# uBlox_camM8_breakout.net
KiCad netlist of a schematic drawn in EAGLE
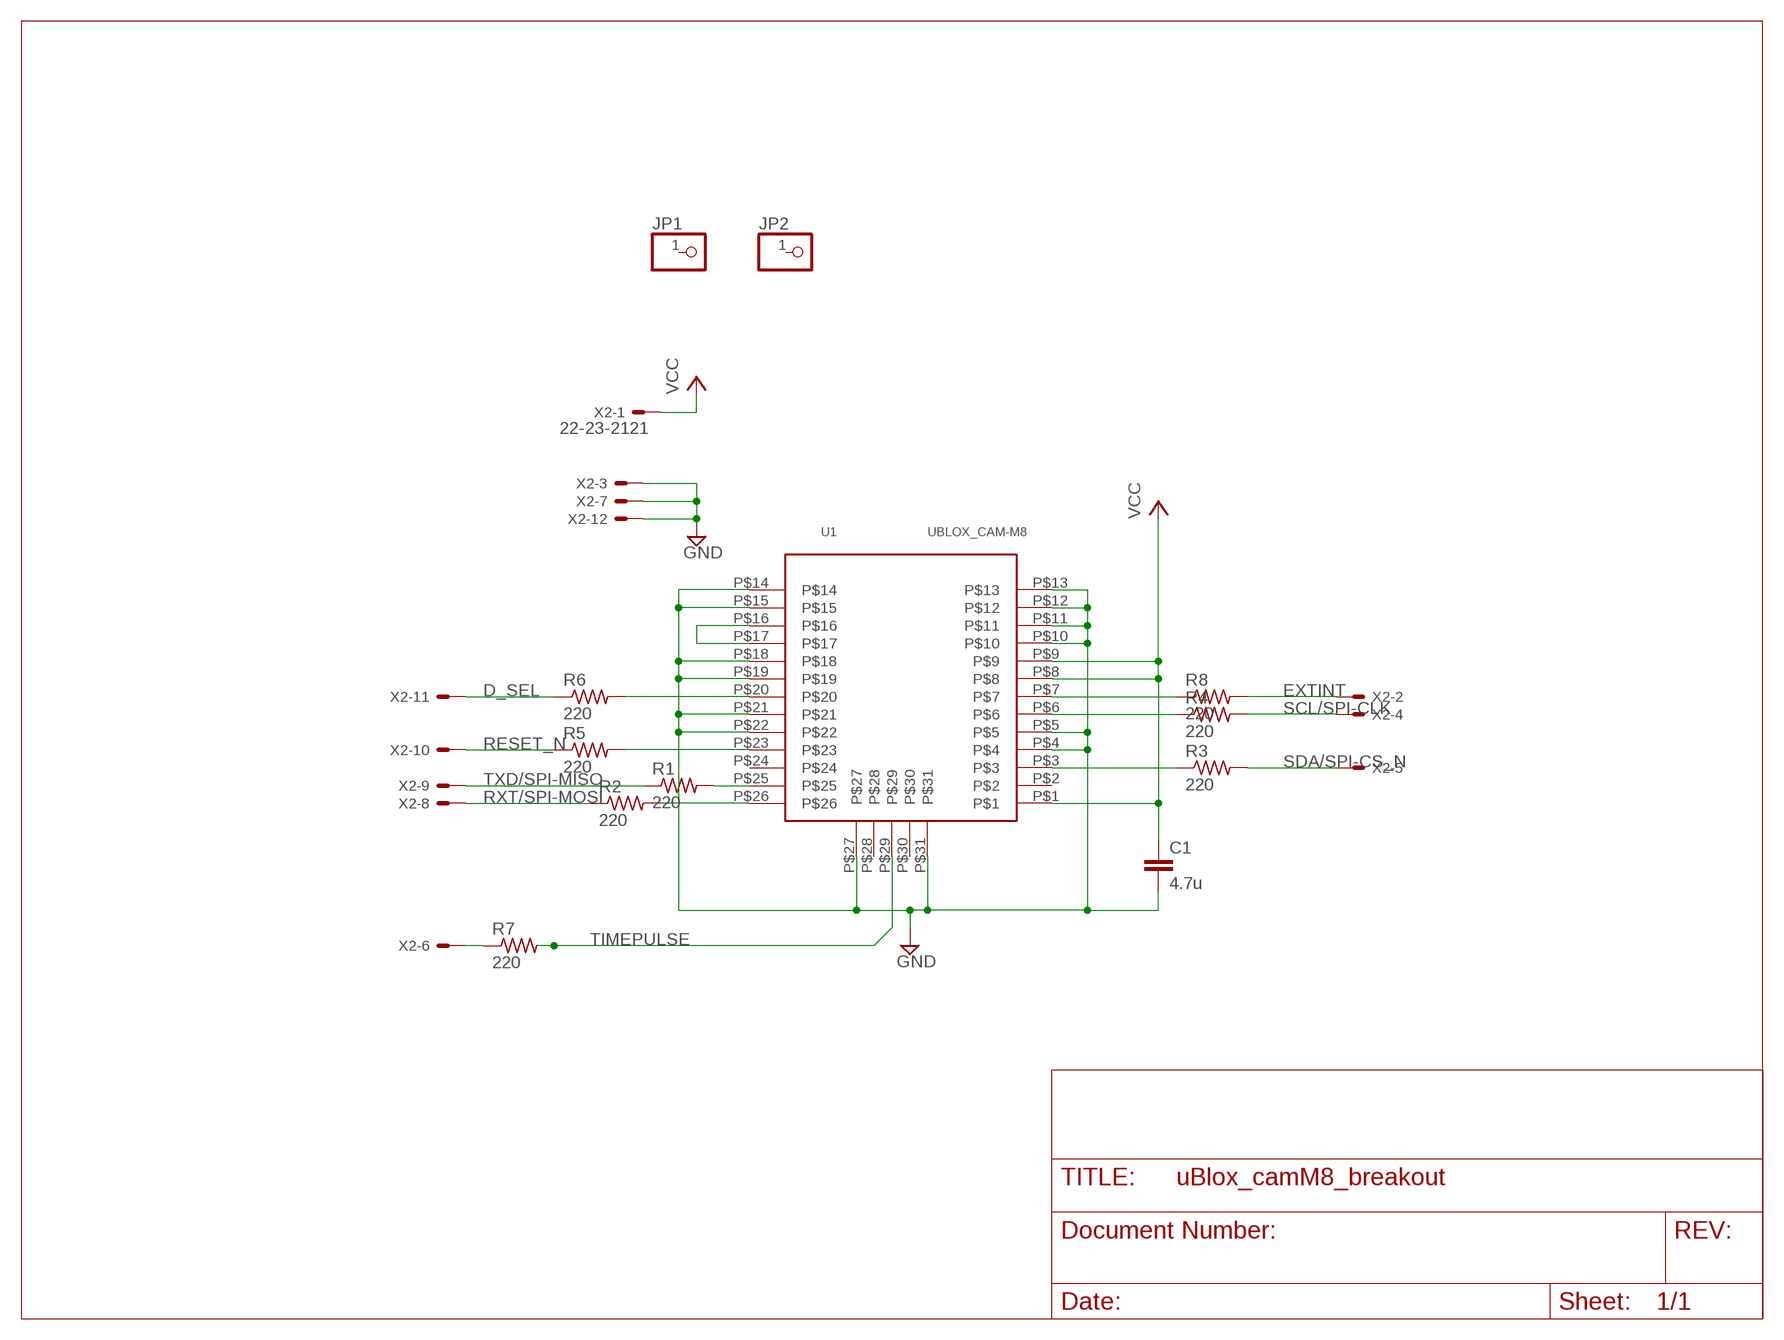
[diagram p0: schematic, sheet 1]

(export (version "E")
  (design (tool "Eeschema 10.0.6"))
  (components
    (comp (ref "C1")
      (value "4.7u")
      (footprint "eagle-import:C0805")
      (libsource (lib "eagle-import") (part "C-EUC0805"))
    )
    (comp (ref "JP1")
      (value "PINHD-1X1")
      (footprint "eagle-import:1X01")
      (libsource (lib "eagle-import") (part "PINHD-1X1"))
    )
    (comp (ref "JP2")
      (value "PINHD-1X1")
      (footprint "eagle-import:1X01")
      (libsource (lib "eagle-import") (part "PINHD-1X1"))
    )
    (comp (ref "R1")
      (value "220")
      (footprint "eagle-import:R0402")
      (libsource (lib "eagle-import") (part "R-US_R0402"))
    )
    (comp (ref "R2")
      (value "220")
      (footprint "eagle-import:R0402")
      (libsource (lib "eagle-import") (part "R-US_R0402"))
    )
    (comp (ref "R3")
      (value "220")
      (footprint "eagle-import:R0402")
      (libsource (lib "eagle-import") (part "R-US_R0402"))
    )
    (comp (ref "R4")
      (value "220")
      (footprint "eagle-import:R0402")
      (libsource (lib "eagle-import") (part "R-US_R0402"))
    )
    (comp (ref "R5")
      (value "220")
      (footprint "eagle-import:R0402")
      (libsource (lib "eagle-import") (part "R-US_R0402"))
    )
    (comp (ref "R6")
      (value "220")
      (footprint "eagle-import:R0402")
      (libsource (lib "eagle-import") (part "R-US_R0402"))
    )
    (comp (ref "R7")
      (value "220")
      (footprint "eagle-import:R0402")
      (libsource (lib "eagle-import") (part "R-US_R0402"))
    )
    (comp (ref "R8")
      (value "220")
      (footprint "eagle-import:R0402")
      (libsource (lib "eagle-import") (part "R-US_R0402"))
    )
    (comp (ref "U1")
      (value "UBLOX_CAM-M8")
      (footprint "eagle-import:UBLOX_CAM-M8")
      (libsource (lib "eagle-import") (part "UBLOX_CAM-M8"))
    )
    (comp (ref "X2")
      (value "22-23-2121")
      (footprint "eagle-import:22-23-2121")
      (fields (field (name "MF") "MOLEX"))
      (libsource (lib "eagle-import") (part "22-23-2121"))
    )
  )
  (nets
    (net (code "1") (name "/D_SEL") (class "Default")
      (node (ref "R6") (pin "1") (pinfunction "1_1") (pintype "passive"))
      (node (ref "X2") (pin "11") (pinfunction "S_11") (pintype "passive"))
    )
    (net (code "2") (name "/EXTINT") (class "Default")
      (node (ref "R8") (pin "2") (pinfunction "2_2") (pintype "passive"))
      (node (ref "X2") (pin "2") (pinfunction "S_2") (pintype "passive"))
    )
    (net (code "3") (name "/RESET_N") (class "Default")
      (node (ref "R5") (pin "1") (pinfunction "1_1") (pintype "passive"))
      (node (ref "X2") (pin "10") (pinfunction "S_10") (pintype "passive"))
    )
    (net (code "4") (name "/RXT{slash}SPI-MOSI") (class "Default")
      (node (ref "R2") (pin "1") (pinfunction "1_1") (pintype "passive"))
      (node (ref "X2") (pin "8") (pinfunction "S_8") (pintype "passive"))
    )
    (net (code "5") (name "/SCL{slash}SPI-CLK") (class "Default")
      (node (ref "R4") (pin "2") (pinfunction "2_2") (pintype "passive"))
      (node (ref "X2") (pin "4") (pinfunction "S_4") (pintype "passive"))
    )
    (net (code "6") (name "/SDA{slash}SPI-CS_N") (class "Default")
      (node (ref "R3") (pin "2") (pinfunction "2_2") (pintype "passive"))
      (node (ref "X2") (pin "5") (pinfunction "S_5") (pintype "passive"))
    )
    (net (code "7") (name "/TIMEPULSE") (class "Default")
      (node (ref "R7") (pin "2") (pinfunction "2_2") (pintype "passive"))
      (node (ref "U1") (pin "P$29") (pinfunction "P$29_P$29") (pintype "bidirectional"))
    )
    (net (code "8") (name "/TXD{slash}SPI-MISO") (class "Default")
      (node (ref "R1") (pin "1") (pinfunction "1_1") (pintype "passive"))
      (node (ref "X2") (pin "9") (pinfunction "S_9") (pintype "passive"))
    )
    (net (code "9") (name "GND") (class "Default")
      (node (ref "C1") (pin "2") (pinfunction "2_2") (pintype "passive"))
      (node (ref "U1") (pin "P$10") (pinfunction "P$10_P$10") (pintype "bidirectional"))
      (node (ref "U1") (pin "P$11") (pinfunction "P$11_P$11") (pintype "bidirectional"))
      (node (ref "U1") (pin "P$12") (pinfunction "P$12_P$12") (pintype "bidirectional"))
      (node (ref "U1") (pin "P$13") (pinfunction "P$13_P$13") (pintype "bidirectional"))
      (node (ref "U1") (pin "P$14") (pinfunction "P$14_P$14") (pintype "bidirectional"))
      (node (ref "U1") (pin "P$15") (pinfunction "P$15_P$15") (pintype "bidirectional"))
      (node (ref "U1") (pin "P$18") (pinfunction "P$18_P$18") (pintype "bidirectional"))
      (node (ref "U1") (pin "P$19") (pinfunction "P$19_P$19") (pintype "bidirectional"))
      (node (ref "U1") (pin "P$21") (pinfunction "P$21_P$21") (pintype "bidirectional"))
      (node (ref "U1") (pin "P$22") (pinfunction "P$22_P$22") (pintype "bidirectional"))
      (node (ref "U1") (pin "P$27") (pinfunction "P$27_P$27") (pintype "bidirectional"))
      (node (ref "U1") (pin "P$31") (pinfunction "P$31_P$31") (pintype "bidirectional"))
      (node (ref "U1") (pin "P$4") (pinfunction "P$4_P$4") (pintype "bidirectional"))
      (node (ref "U1") (pin "P$5") (pinfunction "P$5_P$5") (pintype "bidirectional"))
      (node (ref "X2") (pin "12") (pinfunction "S_12") (pintype "passive"))
      (node (ref "X2") (pin "3") (pinfunction "S_3") (pintype "passive"))
      (node (ref "X2") (pin "7") (pinfunction "S_7") (pintype "passive"))
    )
    (net (code "10") (name "Net-(R1-Pad2)") (class "Default")
      (node (ref "R1") (pin "2") (pinfunction "2_2") (pintype "passive"))
      (node (ref "U1") (pin "P$25") (pinfunction "P$25_P$25") (pintype "bidirectional"))
    )
    (net (code "11") (name "Net-(R2-Pad2)") (class "Default")
      (node (ref "R2") (pin "2") (pinfunction "2_2") (pintype "passive"))
      (node (ref "U1") (pin "P$26") (pinfunction "P$26_P$26") (pintype "bidirectional"))
    )
    (net (code "12") (name "Net-(R3-Pad1)") (class "Default")
      (node (ref "R3") (pin "1") (pinfunction "1_1") (pintype "passive"))
      (node (ref "U1") (pin "P$3") (pinfunction "P$3_P$3") (pintype "bidirectional"))
    )
    (net (code "13") (name "Net-(R4-Pad1)") (class "Default")
      (node (ref "R4") (pin "1") (pinfunction "1_1") (pintype "passive"))
      (node (ref "U1") (pin "P$6") (pinfunction "P$6_P$6") (pintype "bidirectional"))
    )
    (net (code "14") (name "Net-(R5-Pad2)") (class "Default")
      (node (ref "R5") (pin "2") (pinfunction "2_2") (pintype "passive"))
      (node (ref "U1") (pin "P$23") (pinfunction "P$23_P$23") (pintype "bidirectional"))
    )
    (net (code "15") (name "Net-(R6-Pad2)") (class "Default")
      (node (ref "R6") (pin "2") (pinfunction "2_2") (pintype "passive"))
      (node (ref "U1") (pin "P$20") (pinfunction "P$20_P$20") (pintype "bidirectional"))
    )
    (net (code "16") (name "Net-(R8-Pad1)") (class "Default")
      (node (ref "R8") (pin "1") (pinfunction "1_1") (pintype "passive"))
      (node (ref "U1") (pin "P$7") (pinfunction "P$7_P$7") (pintype "bidirectional"))
    )
    (net (code "17") (name "Net-(U1-PadP$16)") (class "Default")
      (node (ref "U1") (pin "P$16") (pinfunction "P$16_P$16") (pintype "bidirectional"))
      (node (ref "U1") (pin "P$17") (pinfunction "P$17_P$17") (pintype "bidirectional"))
    )
    (net (code "18") (name "Net-(X2I-S)") (class "Default")
      (node (ref "R7") (pin "1") (pinfunction "1_1") (pintype "passive"))
      (node (ref "X2") (pin "6") (pinfunction "S_6") (pintype "passive"))
    )
    (net (code "19") (name "VCC") (class "Default")
      (node (ref "C1") (pin "1") (pinfunction "1_1") (pintype "passive"))
      (node (ref "U1") (pin "P$1") (pinfunction "P$1_P$1") (pintype "bidirectional"))
      (node (ref "U1") (pin "P$8") (pinfunction "P$8_P$8") (pintype "bidirectional"))
      (node (ref "U1") (pin "P$9") (pinfunction "P$9_P$9") (pintype "bidirectional"))
      (node (ref "X2") (pin "1") (pinfunction "S_1") (pintype "passive"))
    )
    (net (code "20") (name "unconnected-(JP1-Pad1)") (class "Default")
      (node (ref "JP1") (pin "1") (pinfunction "1_1") (pintype "passive"))
    )
    (net (code "21") (name "unconnected-(JP2-Pad1)") (class "Default")
      (node (ref "JP2") (pin "1") (pinfunction "1_1") (pintype "passive"))
    )
    (net (code "22") (name "unconnected-(U1-PadP$2)") (class "Default")
      (node (ref "U1") (pin "P$2") (pinfunction "P$2_P$2") (pintype "bidirectional"))
    )
    (net (code "23") (name "unconnected-(U1-PadP$24)") (class "Default")
      (node (ref "U1") (pin "P$24") (pinfunction "P$24_P$24") (pintype "bidirectional"))
    )
    (net (code "24") (name "unconnected-(U1-PadP$28)") (class "Default")
      (node (ref "U1") (pin "P$28") (pinfunction "P$28_P$28") (pintype "bidirectional"))
    )
    (net (code "25") (name "unconnected-(U1-PadP$30)") (class "Default")
      (node (ref "U1") (pin "P$30") (pinfunction "P$30_P$30") (pintype "bidirectional"))
    )
  )
)
